# Cell.net
KiCad netlist of a schematic drawn in Altium Designer
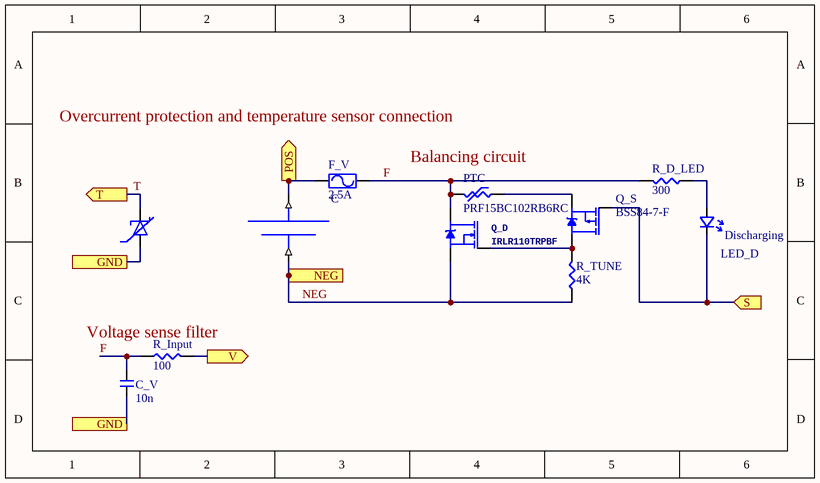
[diagram p0: Cell.SchDoc]

(export (version "E")
  (design (tool "Eeschema 10.0.6"))
  (components
    (comp (ref "C")
      (value "Li1x7pVTC6T with Clip Mounts")
      (footprint "LTC6811:Li1x7pVTC6T_Clips")
      (libsource (lib "LTC6811") (part "Li1x7pVTC6T_Clip"))
    )
    (comp (ref "C_V")
      (value "10n")
      (footprint "CAP-0603")
      (description "CAP-0603")
      (libsource (lib "altium-import") (part "root_1_CAP-0603_"))
    )
    (comp (ref "F_V") (value "2.5A") (footprint "FUSE1206") (libsource (lib "LTC6811") (part "FUSE-1206")))
    (comp (ref "LED_D")
      (value "Discharging")
      (footprint "LED-0603")
      (description "LED-0603")
      (libsource (lib "altium-import") (part "root_3_LED-0603_"))
    )
    (comp (ref "PTC")
      (value "PRF15BC102RB6RC")
      (footprint "NTC-0603")
      (libsource (lib "ife19_Elec_Library") (part "NTC-0603"))
    )
    (comp (ref "Q_D")
      (value "IRLR110TRPBF")
      (footprint "TO252")
      (libsource (lib "LTC6811") (part "NMOS-TO252"))
    )
    (comp (ref "Q_S")
      (value "BSS84-7-F")
      (footprint "SOT23")
      (libsource (lib "ife19_Elec_Library") (part "PMOS-SOT23"))
    )
    (comp (ref "R_D_LED")
      (value "300")
      (footprint "RES-0603")
      (libsource (lib "altium-import") (part "root_2_RES-0603_"))
    )
    (comp (ref "R_Input")
      (value "100")
      (footprint "RES-0603")
      (libsource (lib "altium-import") (part "root_0_RES-0603_"))
    )
    (comp (ref "R_TUNE")
      (value "4K")
      (footprint "RES-0603")
      (libsource (lib "ife19_Elec_Library") (part "RES-0603"))
    )
  )
  (nets
    (net (code "1") (name "/F") (class "Default")
      (node (ref "C_V") (pin "2") (pinfunction "2_2") (pintype "passive"))
      (node (ref "F_V") (pin "2") (pinfunction "2_2") (pintype "passive"))
      (node (ref "PTC") (pin "2") (pinfunction "2_2") (pintype "passive"))
      (node (ref "Q_D") (pin "2") (pinfunction "D_2") (pintype "passive"))
      (node (ref "R_D_LED") (pin "2") (pinfunction "2_2") (pintype "passive"))
      (node (ref "R_Input") (pin "1") (pinfunction "1_1") (pintype "passive"))
    )
    (net (code "2") (name "/GND") (class "Default")
      (node (ref "C") (pin "T-") (pinfunction "T-_T-") (pintype "passive"))
      (node (ref "C_V") (pin "1") (pinfunction "1_1") (pintype "passive"))
    )
    (net (code "3") (name "/NEG") (class "Default")
      (node (ref "C") (pin "-") (pinfunction "-_-") (pintype "input"))
      (node (ref "Q_D") (pin "3") (pinfunction "S_3") (pintype "passive"))
      (node (ref "R_TUNE") (pin "1") (pinfunction "1_1") (pintype "passive"))
    )
    (net (code "4") (name "/POS") (class "Default")
      (node (ref "C") (pin "+") (pinfunction "+_+") (pintype "output"))
      (node (ref "F_V") (pin "1") (pinfunction "1_1") (pintype "passive"))
    )
    (net (code "5") (name "/S") (class "Default")
      (node (ref "LED_D") (pin "K") (pinfunction "K_K") (pintype "passive"))
      (node (ref "Q_S") (pin "1") (pinfunction "G_1") (pintype "passive"))
    )
    (net (code "6") (name "/T") (class "Default")
      (node (ref "C") (pin "T+") (pinfunction "T+_T+") (pintype "passive"))
    )
    (net (code "7") (name "/V") (class "Default")
      (node (ref "R_Input") (pin "2") (pinfunction "2_2") (pintype "passive"))
    )
    (net (code "8") (name "Net-(LED_D-PadA)") (class "Default")
      (node (ref "LED_D") (pin "A") (pinfunction "A_A") (pintype "passive"))
      (node (ref "R_D_LED") (pin "1") (pinfunction "1_1") (pintype "passive"))
    )
    (net (code "9") (name "Net-(Q_D-G)") (class "Default")
      (node (ref "Q_D") (pin "1") (pinfunction "G_1") (pintype "passive"))
      (node (ref "Q_S") (pin "3") (pinfunction "D_3") (pintype "passive"))
      (node (ref "R_TUNE") (pin "2") (pinfunction "2_2") (pintype "passive"))
    )
    (net (code "10") (name "Net-(Q_S-S)") (class "Default")
      (node (ref "PTC") (pin "1") (pinfunction "1_1") (pintype "passive"))
      (node (ref "Q_S") (pin "2") (pinfunction "S_2") (pintype "passive"))
    )
  )
)
